# F6O2JSZITCH0EP8_1.net
KiCad netlist of a schematic drawn in EAGLE
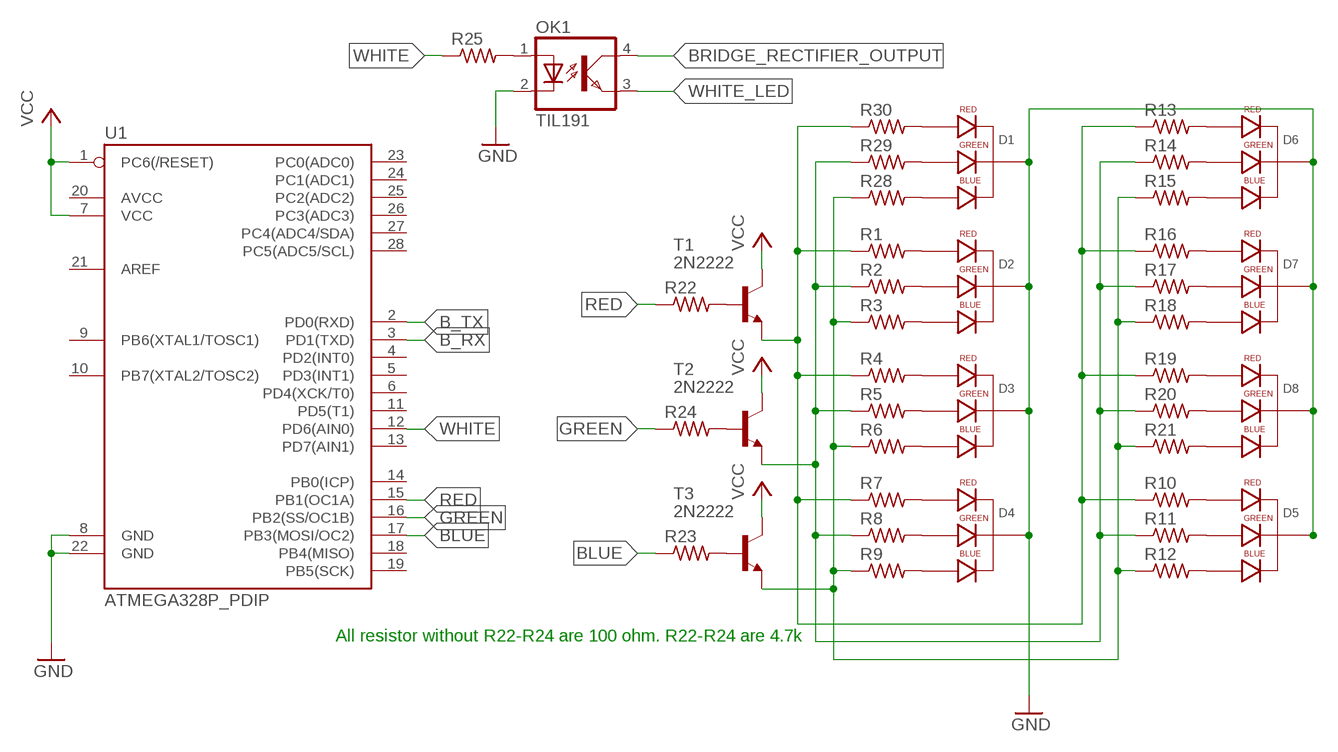
[diagram p0: schematic, sheet 1]

(export (version "E")
  (design (tool "Eeschema 10.0.6"))
  (components
    (comp (ref "D1")
      (value "LED-RGB-CC-THRUCLEAR")
      (footprint "eagle-import:LED-RGB-THRU")
      (libsource (lib "eagle-import") (part "LED-RGB-CC-THRUCLEAR"))
    )
    (comp (ref "D2")
      (value "LED-RGB-CC-THRUCLEAR")
      (footprint "eagle-import:LED-RGB-THRU")
      (libsource (lib "eagle-import") (part "LED-RGB-CC-THRUCLEAR"))
    )
    (comp (ref "D3")
      (value "LED-RGB-CC-THRUCLEAR")
      (footprint "eagle-import:LED-RGB-THRU")
      (libsource (lib "eagle-import") (part "LED-RGB-CC-THRUCLEAR"))
    )
    (comp (ref "D4")
      (value "LED-RGB-CC-THRUCLEAR")
      (footprint "eagle-import:LED-RGB-THRU")
      (libsource (lib "eagle-import") (part "LED-RGB-CC-THRUCLEAR"))
    )
    (comp (ref "D5")
      (value "LED-RGB-CC-THRUCLEAR")
      (footprint "eagle-import:LED-RGB-THRU")
      (libsource (lib "eagle-import") (part "LED-RGB-CC-THRUCLEAR"))
    )
    (comp (ref "D6")
      (value "LED-RGB-CC-THRUCLEAR")
      (footprint "eagle-import:LED-RGB-THRU")
      (libsource (lib "eagle-import") (part "LED-RGB-CC-THRUCLEAR"))
    )
    (comp (ref "D7")
      (value "LED-RGB-CC-THRUCLEAR")
      (footprint "eagle-import:LED-RGB-THRU")
      (libsource (lib "eagle-import") (part "LED-RGB-CC-THRUCLEAR"))
    )
    (comp (ref "D8")
      (value "LED-RGB-CC-THRUCLEAR")
      (footprint "eagle-import:LED-RGB-THRU")
      (libsource (lib "eagle-import") (part "LED-RGB-CC-THRUCLEAR"))
    )
    (comp (ref "OK1")
      (value "TIL191")
      (footprint "eagle-import:DIL04")
      (libsource (lib "eagle-import") (part "TIL191"))
    )
    (comp (ref "R1")
      (value "R-US_0309/10")
      (footprint "eagle-import:0309_10")
      (libsource (lib "eagle-import") (part "R-US_0309/10"))
    )
    (comp (ref "R2")
      (value "R-US_0309/10")
      (footprint "eagle-import:0309_10")
      (libsource (lib "eagle-import") (part "R-US_0309/10"))
    )
    (comp (ref "R3")
      (value "R-US_0309/10")
      (footprint "eagle-import:0309_10")
      (libsource (lib "eagle-import") (part "R-US_0309/10"))
    )
    (comp (ref "R4")
      (value "R-US_0309/10")
      (footprint "eagle-import:0309_10")
      (libsource (lib "eagle-import") (part "R-US_0309/10"))
    )
    (comp (ref "R5")
      (value "R-US_0309/10")
      (footprint "eagle-import:0309_10")
      (libsource (lib "eagle-import") (part "R-US_0309/10"))
    )
    (comp (ref "R6")
      (value "R-US_0309/10")
      (footprint "eagle-import:0309_10")
      (libsource (lib "eagle-import") (part "R-US_0309/10"))
    )
    (comp (ref "R7")
      (value "R-US_0309/10")
      (footprint "eagle-import:0309_10")
      (libsource (lib "eagle-import") (part "R-US_0309/10"))
    )
    (comp (ref "R8")
      (value "R-US_0309/10")
      (footprint "eagle-import:0309_10")
      (libsource (lib "eagle-import") (part "R-US_0309/10"))
    )
    (comp (ref "R9")
      (value "R-US_0309/10")
      (footprint "eagle-import:0309_10")
      (libsource (lib "eagle-import") (part "R-US_0309/10"))
    )
    (comp (ref "R10")
      (value "R-US_0309/10")
      (footprint "eagle-import:0309_10")
      (libsource (lib "eagle-import") (part "R-US_0309/10"))
    )
    (comp (ref "R11")
      (value "R-US_0309/10")
      (footprint "eagle-import:0309_10")
      (libsource (lib "eagle-import") (part "R-US_0309/10"))
    )
    (comp (ref "R12")
      (value "R-US_0309/10")
      (footprint "eagle-import:0309_10")
      (libsource (lib "eagle-import") (part "R-US_0309/10"))
    )
    (comp (ref "R13")
      (value "R-US_0309/10")
      (footprint "eagle-import:0309_10")
      (libsource (lib "eagle-import") (part "R-US_0309/10"))
    )
    (comp (ref "R14")
      (value "R-US_0309/10")
      (footprint "eagle-import:0309_10")
      (libsource (lib "eagle-import") (part "R-US_0309/10"))
    )
    (comp (ref "R15")
      (value "R-US_0309/10")
      (footprint "eagle-import:0309_10")
      (libsource (lib "eagle-import") (part "R-US_0309/10"))
    )
    (comp (ref "R16")
      (value "R-US_0309/10")
      (footprint "eagle-import:0309_10")
      (libsource (lib "eagle-import") (part "R-US_0309/10"))
    )
    (comp (ref "R17")
      (value "R-US_0309/10")
      (footprint "eagle-import:0309_10")
      (libsource (lib "eagle-import") (part "R-US_0309/10"))
    )
    (comp (ref "R18")
      (value "R-US_0309/10")
      (footprint "eagle-import:0309_10")
      (libsource (lib "eagle-import") (part "R-US_0309/10"))
    )
    (comp (ref "R19")
      (value "R-US_0309/10")
      (footprint "eagle-import:0309_10")
      (libsource (lib "eagle-import") (part "R-US_0309/10"))
    )
    (comp (ref "R20")
      (value "R-US_0309/10")
      (footprint "eagle-import:0309_10")
      (libsource (lib "eagle-import") (part "R-US_0309/10"))
    )
    (comp (ref "R21")
      (value "R-US_0309/10")
      (footprint "eagle-import:0309_10")
      (libsource (lib "eagle-import") (part "R-US_0309/10"))
    )
    (comp (ref "R22")
      (value "R-US_0309/10")
      (footprint "eagle-import:0309_10")
      (libsource (lib "eagle-import") (part "R-US_0309/10"))
    )
    (comp (ref "R23")
      (value "R-US_0309/10")
      (footprint "eagle-import:0309_10")
      (libsource (lib "eagle-import") (part "R-US_0309/10"))
    )
    (comp (ref "R24")
      (value "R-US_0309/10")
      (footprint "eagle-import:0309_10")
      (libsource (lib "eagle-import") (part "R-US_0309/10"))
    )
    (comp (ref "R25")
      (value "R-US_0309/10")
      (footprint "eagle-import:0309_10")
      (libsource (lib "eagle-import") (part "R-US_0309/10"))
    )
    (comp (ref "R28")
      (value "R-US_0309/10")
      (footprint "eagle-import:0309_10")
      (libsource (lib "eagle-import") (part "R-US_0309/10"))
    )
    (comp (ref "R29")
      (value "R-US_0309/10")
      (footprint "eagle-import:0309_10")
      (libsource (lib "eagle-import") (part "R-US_0309/10"))
    )
    (comp (ref "R30")
      (value "R-US_0309/10")
      (footprint "eagle-import:0309_10")
      (libsource (lib "eagle-import") (part "R-US_0309/10"))
    )
    (comp (ref "T1")
      (value "2N2222")
      (footprint "eagle-import:TO18")
      (libsource (lib "eagle-import") (part "2N2222"))
    )
    (comp (ref "T2")
      (value "2N2222")
      (footprint "eagle-import:TO18")
      (libsource (lib "eagle-import") (part "2N2222"))
    )
    (comp (ref "T3")
      (value "2N2222")
      (footprint "eagle-import:TO18")
      (libsource (lib "eagle-import") (part "2N2222"))
    )
    (comp (ref "U1")
      (value "ATMEGA328P_PDIP")
      (footprint "eagle-import:DIL28-3")
      (libsource (lib "eagle-import") (part "ATMEGA328P_PDIP"))
    )
  )
  (nets
    (net (code "1") (name "BLUE") (class "Default")
      (node (ref "R23") (pin "1") (pinfunction "1_1") (pintype "passive"))
      (node (ref "U1") (pin "17") (pinfunction "PB3(MOSI/OC2)_17") (pintype "bidirectional"))
    )
    (net (code "2") (name "BRIDGE_RECTIFIER_OUTPUT") (class "Default")
      (node (ref "OK1") (pin "4") (pinfunction "COL_4") (pintype "passive"))
    )
    (net (code "3") (name "B_RX") (class "Default")
      (node (ref "U1") (pin "3") (pinfunction "PD1(TXD)_3") (pintype "bidirectional"))
    )
    (net (code "4") (name "B_TX") (class "Default")
      (node (ref "U1") (pin "2") (pinfunction "PD0(RXD)_2") (pintype "bidirectional"))
    )
    (net (code "5") (name "GND") (class "Default")
      (node (ref "D1") (pin "2") (pinfunction "CATHODE_2") (pintype "bidirectional"))
      (node (ref "D2") (pin "2") (pinfunction "CATHODE_2") (pintype "bidirectional"))
      (node (ref "D3") (pin "2") (pinfunction "CATHODE_2") (pintype "bidirectional"))
      (node (ref "D4") (pin "2") (pinfunction "CATHODE_2") (pintype "bidirectional"))
      (node (ref "D5") (pin "2") (pinfunction "CATHODE_2") (pintype "bidirectional"))
      (node (ref "D6") (pin "2") (pinfunction "CATHODE_2") (pintype "bidirectional"))
      (node (ref "D7") (pin "2") (pinfunction "CATHODE_2") (pintype "bidirectional"))
      (node (ref "D8") (pin "2") (pinfunction "CATHODE_2") (pintype "bidirectional"))
      (node (ref "OK1") (pin "2") (pinfunction "C_2") (pintype "passive"))
      (node (ref "U1") (pin "22") (pinfunction "GND_22") (pintype "bidirectional"))
      (node (ref "U1") (pin "8") (pinfunction "GND_8") (pintype "bidirectional"))
    )
    (net (code "6") (name "GREEN") (class "Default")
      (node (ref "R24") (pin "1") (pinfunction "1_1") (pintype "passive"))
      (node (ref "U1") (pin "16") (pinfunction "PB2(SS/OC1B)_16") (pintype "bidirectional"))
    )
    (net (code "7") (name "Net-(D1-BLUE_CATHODE)") (class "Default")
      (node (ref "D1") (pin "4") (pinfunction "BLUE_CATHODE_4") (pintype "bidirectional"))
      (node (ref "R28") (pin "2") (pinfunction "2_2") (pintype "passive"))
    )
    (net (code "8") (name "Net-(D1-GREEN_CATHODE)") (class "Default")
      (node (ref "D1") (pin "3") (pinfunction "GREEN_CATHODE_3") (pintype "bidirectional"))
      (node (ref "R29") (pin "2") (pinfunction "2_2") (pintype "passive"))
    )
    (net (code "9") (name "Net-(D1-RED_CATHODE)") (class "Default")
      (node (ref "D1") (pin "1") (pinfunction "RED_CATHODE_1") (pintype "bidirectional"))
      (node (ref "R30") (pin "2") (pinfunction "2_2") (pintype "passive"))
    )
    (net (code "10") (name "Net-(D2-BLUE_CATHODE)") (class "Default")
      (node (ref "D2") (pin "4") (pinfunction "BLUE_CATHODE_4") (pintype "bidirectional"))
      (node (ref "R3") (pin "2") (pinfunction "2_2") (pintype "passive"))
    )
    (net (code "11") (name "Net-(D2-GREEN_CATHODE)") (class "Default")
      (node (ref "D2") (pin "3") (pinfunction "GREEN_CATHODE_3") (pintype "bidirectional"))
      (node (ref "R2") (pin "2") (pinfunction "2_2") (pintype "passive"))
    )
    (net (code "12") (name "Net-(D2-RED_CATHODE)") (class "Default")
      (node (ref "D2") (pin "1") (pinfunction "RED_CATHODE_1") (pintype "bidirectional"))
      (node (ref "R1") (pin "2") (pinfunction "2_2") (pintype "passive"))
    )
    (net (code "13") (name "Net-(D3-BLUE_CATHODE)") (class "Default")
      (node (ref "D3") (pin "4") (pinfunction "BLUE_CATHODE_4") (pintype "bidirectional"))
      (node (ref "R6") (pin "2") (pinfunction "2_2") (pintype "passive"))
    )
    (net (code "14") (name "Net-(D3-GREEN_CATHODE)") (class "Default")
      (node (ref "D3") (pin "3") (pinfunction "GREEN_CATHODE_3") (pintype "bidirectional"))
      (node (ref "R5") (pin "2") (pinfunction "2_2") (pintype "passive"))
    )
    (net (code "15") (name "Net-(D3-RED_CATHODE)") (class "Default")
      (node (ref "D3") (pin "1") (pinfunction "RED_CATHODE_1") (pintype "bidirectional"))
      (node (ref "R4") (pin "2") (pinfunction "2_2") (pintype "passive"))
    )
    (net (code "16") (name "Net-(D4-BLUE_CATHODE)") (class "Default")
      (node (ref "D4") (pin "4") (pinfunction "BLUE_CATHODE_4") (pintype "bidirectional"))
      (node (ref "R9") (pin "2") (pinfunction "2_2") (pintype "passive"))
    )
    (net (code "17") (name "Net-(D4-GREEN_CATHODE)") (class "Default")
      (node (ref "D4") (pin "3") (pinfunction "GREEN_CATHODE_3") (pintype "bidirectional"))
      (node (ref "R8") (pin "2") (pinfunction "2_2") (pintype "passive"))
    )
    (net (code "18") (name "Net-(D4-RED_CATHODE)") (class "Default")
      (node (ref "D4") (pin "1") (pinfunction "RED_CATHODE_1") (pintype "bidirectional"))
      (node (ref "R7") (pin "2") (pinfunction "2_2") (pintype "passive"))
    )
    (net (code "19") (name "Net-(D5-BLUE_CATHODE)") (class "Default")
      (node (ref "D5") (pin "4") (pinfunction "BLUE_CATHODE_4") (pintype "bidirectional"))
      (node (ref "R12") (pin "2") (pinfunction "2_2") (pintype "passive"))
    )
    (net (code "20") (name "Net-(D5-GREEN_CATHODE)") (class "Default")
      (node (ref "D5") (pin "3") (pinfunction "GREEN_CATHODE_3") (pintype "bidirectional"))
      (node (ref "R11") (pin "2") (pinfunction "2_2") (pintype "passive"))
    )
    (net (code "21") (name "Net-(D5-RED_CATHODE)") (class "Default")
      (node (ref "D5") (pin "1") (pinfunction "RED_CATHODE_1") (pintype "bidirectional"))
      (node (ref "R10") (pin "2") (pinfunction "2_2") (pintype "passive"))
    )
    (net (code "22") (name "Net-(D6-BLUE_CATHODE)") (class "Default")
      (node (ref "D6") (pin "4") (pinfunction "BLUE_CATHODE_4") (pintype "bidirectional"))
      (node (ref "R15") (pin "2") (pinfunction "2_2") (pintype "passive"))
    )
    (net (code "23") (name "Net-(D6-GREEN_CATHODE)") (class "Default")
      (node (ref "D6") (pin "3") (pinfunction "GREEN_CATHODE_3") (pintype "bidirectional"))
      (node (ref "R14") (pin "2") (pinfunction "2_2") (pintype "passive"))
    )
    (net (code "24") (name "Net-(D6-RED_CATHODE)") (class "Default")
      (node (ref "D6") (pin "1") (pinfunction "RED_CATHODE_1") (pintype "bidirectional"))
      (node (ref "R13") (pin "2") (pinfunction "2_2") (pintype "passive"))
    )
    (net (code "25") (name "Net-(D7-BLUE_CATHODE)") (class "Default")
      (node (ref "D7") (pin "4") (pinfunction "BLUE_CATHODE_4") (pintype "bidirectional"))
      (node (ref "R18") (pin "2") (pinfunction "2_2") (pintype "passive"))
    )
    (net (code "26") (name "Net-(D7-GREEN_CATHODE)") (class "Default")
      (node (ref "D7") (pin "3") (pinfunction "GREEN_CATHODE_3") (pintype "bidirectional"))
      (node (ref "R17") (pin "2") (pinfunction "2_2") (pintype "passive"))
    )
    (net (code "27") (name "Net-(D7-RED_CATHODE)") (class "Default")
      (node (ref "D7") (pin "1") (pinfunction "RED_CATHODE_1") (pintype "bidirectional"))
      (node (ref "R16") (pin "2") (pinfunction "2_2") (pintype "passive"))
    )
    (net (code "28") (name "Net-(D8-BLUE_CATHODE)") (class "Default")
      (node (ref "D8") (pin "4") (pinfunction "BLUE_CATHODE_4") (pintype "bidirectional"))
      (node (ref "R21") (pin "2") (pinfunction "2_2") (pintype "passive"))
    )
    (net (code "29") (name "Net-(D8-GREEN_CATHODE)") (class "Default")
      (node (ref "D8") (pin "3") (pinfunction "GREEN_CATHODE_3") (pintype "bidirectional"))
      (node (ref "R20") (pin "2") (pinfunction "2_2") (pintype "passive"))
    )
    (net (code "30") (name "Net-(D8-RED_CATHODE)") (class "Default")
      (node (ref "D8") (pin "1") (pinfunction "RED_CATHODE_1") (pintype "bidirectional"))
      (node (ref "R19") (pin "2") (pinfunction "2_2") (pintype "passive"))
    )
    (net (code "31") (name "Net-(OK1-A)") (class "Default")
      (node (ref "OK1") (pin "1") (pinfunction "A_1") (pintype "passive"))
      (node (ref "R25") (pin "2") (pinfunction "2_2") (pintype "passive"))
    )
    (net (code "32") (name "Net-(T1-B)") (class "Default")
      (node (ref "R22") (pin "2") (pinfunction "2_2") (pintype "passive"))
      (node (ref "T1") (pin "2") (pinfunction "B_2") (pintype "passive"))
    )
    (net (code "33") (name "Net-(T1-E)") (class "Default")
      (node (ref "R1") (pin "1") (pinfunction "1_1") (pintype "passive"))
      (node (ref "R10") (pin "1") (pinfunction "1_1") (pintype "passive"))
      (node (ref "R13") (pin "1") (pinfunction "1_1") (pintype "passive"))
      (node (ref "R16") (pin "1") (pinfunction "1_1") (pintype "passive"))
      (node (ref "R19") (pin "1") (pinfunction "1_1") (pintype "passive"))
      (node (ref "R30") (pin "1") (pinfunction "1_1") (pintype "passive"))
      (node (ref "R4") (pin "1") (pinfunction "1_1") (pintype "passive"))
      (node (ref "R7") (pin "1") (pinfunction "1_1") (pintype "passive"))
      (node (ref "T1") (pin "1") (pinfunction "E_1") (pintype "passive"))
    )
    (net (code "34") (name "Net-(T2-B)") (class "Default")
      (node (ref "R24") (pin "2") (pinfunction "2_2") (pintype "passive"))
      (node (ref "T2") (pin "2") (pinfunction "B_2") (pintype "passive"))
    )
    (net (code "35") (name "Net-(T2-E)") (class "Default")
      (node (ref "R11") (pin "1") (pinfunction "1_1") (pintype "passive"))
      (node (ref "R14") (pin "1") (pinfunction "1_1") (pintype "passive"))
      (node (ref "R17") (pin "1") (pinfunction "1_1") (pintype "passive"))
      (node (ref "R2") (pin "1") (pinfunction "1_1") (pintype "passive"))
      (node (ref "R20") (pin "1") (pinfunction "1_1") (pintype "passive"))
      (node (ref "R29") (pin "1") (pinfunction "1_1") (pintype "passive"))
      (node (ref "R5") (pin "1") (pinfunction "1_1") (pintype "passive"))
      (node (ref "R8") (pin "1") (pinfunction "1_1") (pintype "passive"))
      (node (ref "T2") (pin "1") (pinfunction "E_1") (pintype "passive"))
    )
    (net (code "36") (name "Net-(T3-B)") (class "Default")
      (node (ref "R23") (pin "2") (pinfunction "2_2") (pintype "passive"))
      (node (ref "T3") (pin "2") (pinfunction "B_2") (pintype "passive"))
    )
    (net (code "37") (name "Net-(T3-E)") (class "Default")
      (node (ref "R12") (pin "1") (pinfunction "1_1") (pintype "passive"))
      (node (ref "R15") (pin "1") (pinfunction "1_1") (pintype "passive"))
      (node (ref "R18") (pin "1") (pinfunction "1_1") (pintype "passive"))
      (node (ref "R21") (pin "1") (pinfunction "1_1") (pintype "passive"))
      (node (ref "R28") (pin "1") (pinfunction "1_1") (pintype "passive"))
      (node (ref "R3") (pin "1") (pinfunction "1_1") (pintype "passive"))
      (node (ref "R6") (pin "1") (pinfunction "1_1") (pintype "passive"))
      (node (ref "R9") (pin "1") (pinfunction "1_1") (pintype "passive"))
      (node (ref "T3") (pin "1") (pinfunction "E_1") (pintype "passive"))
    )
    (net (code "38") (name "RED") (class "Default")
      (node (ref "R22") (pin "1") (pinfunction "1_1") (pintype "passive"))
      (node (ref "U1") (pin "15") (pinfunction "PB1(OC1A)_15") (pintype "bidirectional"))
    )
    (net (code "39") (name "VCC") (class "Default")
      (node (ref "T1") (pin "3") (pinfunction "C_3") (pintype "passive"))
      (node (ref "T2") (pin "3") (pinfunction "C_3") (pintype "passive"))
      (node (ref "T3") (pin "3") (pinfunction "C_3") (pintype "passive"))
      (node (ref "U1") (pin "1") (pinfunction "PC6(/RESET)_1") (pintype "bidirectional"))
      (node (ref "U1") (pin "7") (pinfunction "VCC_7") (pintype "bidirectional"))
    )
    (net (code "40") (name "WHITE") (class "Default")
      (node (ref "R25") (pin "1") (pinfunction "1_1") (pintype "passive"))
      (node (ref "U1") (pin "12") (pinfunction "PD6(AIN0)_12") (pintype "bidirectional"))
    )
    (net (code "41") (name "WHITE_LED") (class "Default")
      (node (ref "OK1") (pin "3") (pinfunction "EMIT_3") (pintype "passive"))
    )
    (net (code "42") (name "unconnected-(U1-AREF-Pad21)") (class "Default")
      (node (ref "U1") (pin "21") (pinfunction "AREF_21") (pintype "bidirectional"))
    )
    (net (code "43") (name "unconnected-(U1-AVCC-Pad20)") (class "Default")
      (node (ref "U1") (pin "20") (pinfunction "AVCC_20") (pintype "bidirectional"))
    )
    (net (code "44") (name "unconnected-(U1-PB0(ICP)-Pad14)") (class "Default")
      (node (ref "U1") (pin "14") (pinfunction "PB0(ICP)_14") (pintype "bidirectional"))
    )
    (net (code "45") (name "unconnected-(U1-PB4(MISO)-Pad18)") (class "Default")
      (node (ref "U1") (pin "18") (pinfunction "PB4(MISO)_18") (pintype "bidirectional"))
    )
    (net (code "46") (name "unconnected-(U1-PB5(SCK)-Pad19)") (class "Default")
      (node (ref "U1") (pin "19") (pinfunction "PB5(SCK)_19") (pintype "bidirectional"))
    )
    (net (code "47") (name "unconnected-(U1-PB6(XTAL1{slash}TOSC1)-Pad9)") (class "Default")
      (node (ref "U1") (pin "9") (pinfunction "PB6(XTAL1/TOSC1)_9") (pintype "bidirectional"))
    )
    (net (code "48") (name "unconnected-(U1-PB7(XTAL2{slash}TOSC2)-Pad10)") (class "Default")
      (node (ref "U1") (pin "10") (pinfunction "PB7(XTAL2/TOSC2)_10") (pintype "bidirectional"))
    )
    (net (code "49") (name "unconnected-(U1-PC0(ADC0)-Pad23)") (class "Default")
      (node (ref "U1") (pin "23") (pinfunction "PC0(ADC0)_23") (pintype "bidirectional"))
    )
    (net (code "50") (name "unconnected-(U1-PC1(ADC1)-Pad24)") (class "Default")
      (node (ref "U1") (pin "24") (pinfunction "PC1(ADC1)_24") (pintype "bidirectional"))
    )
    (net (code "51") (name "unconnected-(U1-PC2(ADC2)-Pad25)") (class "Default")
      (node (ref "U1") (pin "25") (pinfunction "PC2(ADC2)_25") (pintype "bidirectional"))
    )
    (net (code "52") (name "unconnected-(U1-PC3(ADC3)-Pad26)") (class "Default")
      (node (ref "U1") (pin "26") (pinfunction "PC3(ADC3)_26") (pintype "bidirectional"))
    )
    (net (code "53") (name "unconnected-(U1-PC4(ADC4{slash}SDA)-Pad27)") (class "Default")
      (node (ref "U1") (pin "27") (pinfunction "PC4(ADC4/SDA)_27") (pintype "bidirectional"))
    )
    (net (code "54") (name "unconnected-(U1-PC5(ADC5{slash}SCL)-Pad28)") (class "Default")
      (node (ref "U1") (pin "28") (pinfunction "PC5(ADC5/SCL)_28") (pintype "bidirectional"))
    )
    (net (code "55") (name "unconnected-(U1-PD2(INT0)-Pad4)") (class "Default")
      (node (ref "U1") (pin "4") (pinfunction "PD2(INT0)_4") (pintype "bidirectional"))
    )
    (net (code "56") (name "unconnected-(U1-PD3(INT1)-Pad5)") (class "Default")
      (node (ref "U1") (pin "5") (pinfunction "PD3(INT1)_5") (pintype "bidirectional"))
    )
    (net (code "57") (name "unconnected-(U1-PD4(XCK{slash}T0)-Pad6)") (class "Default")
      (node (ref "U1") (pin "6") (pinfunction "PD4(XCK/T0)_6") (pintype "bidirectional"))
    )
    (net (code "58") (name "unconnected-(U1-PD5(T1)-Pad11)") (class "Default")
      (node (ref "U1") (pin "11") (pinfunction "PD5(T1)_11") (pintype "bidirectional"))
    )
    (net (code "59") (name "unconnected-(U1-PD7(AIN1)-Pad13)") (class "Default")
      (node (ref "U1") (pin "13") (pinfunction "PD7(AIN1)_13") (pintype "bidirectional"))
    )
  )
)
